# POWER_REG.net
KiCad netlist of a schematic drawn in Altium Designer
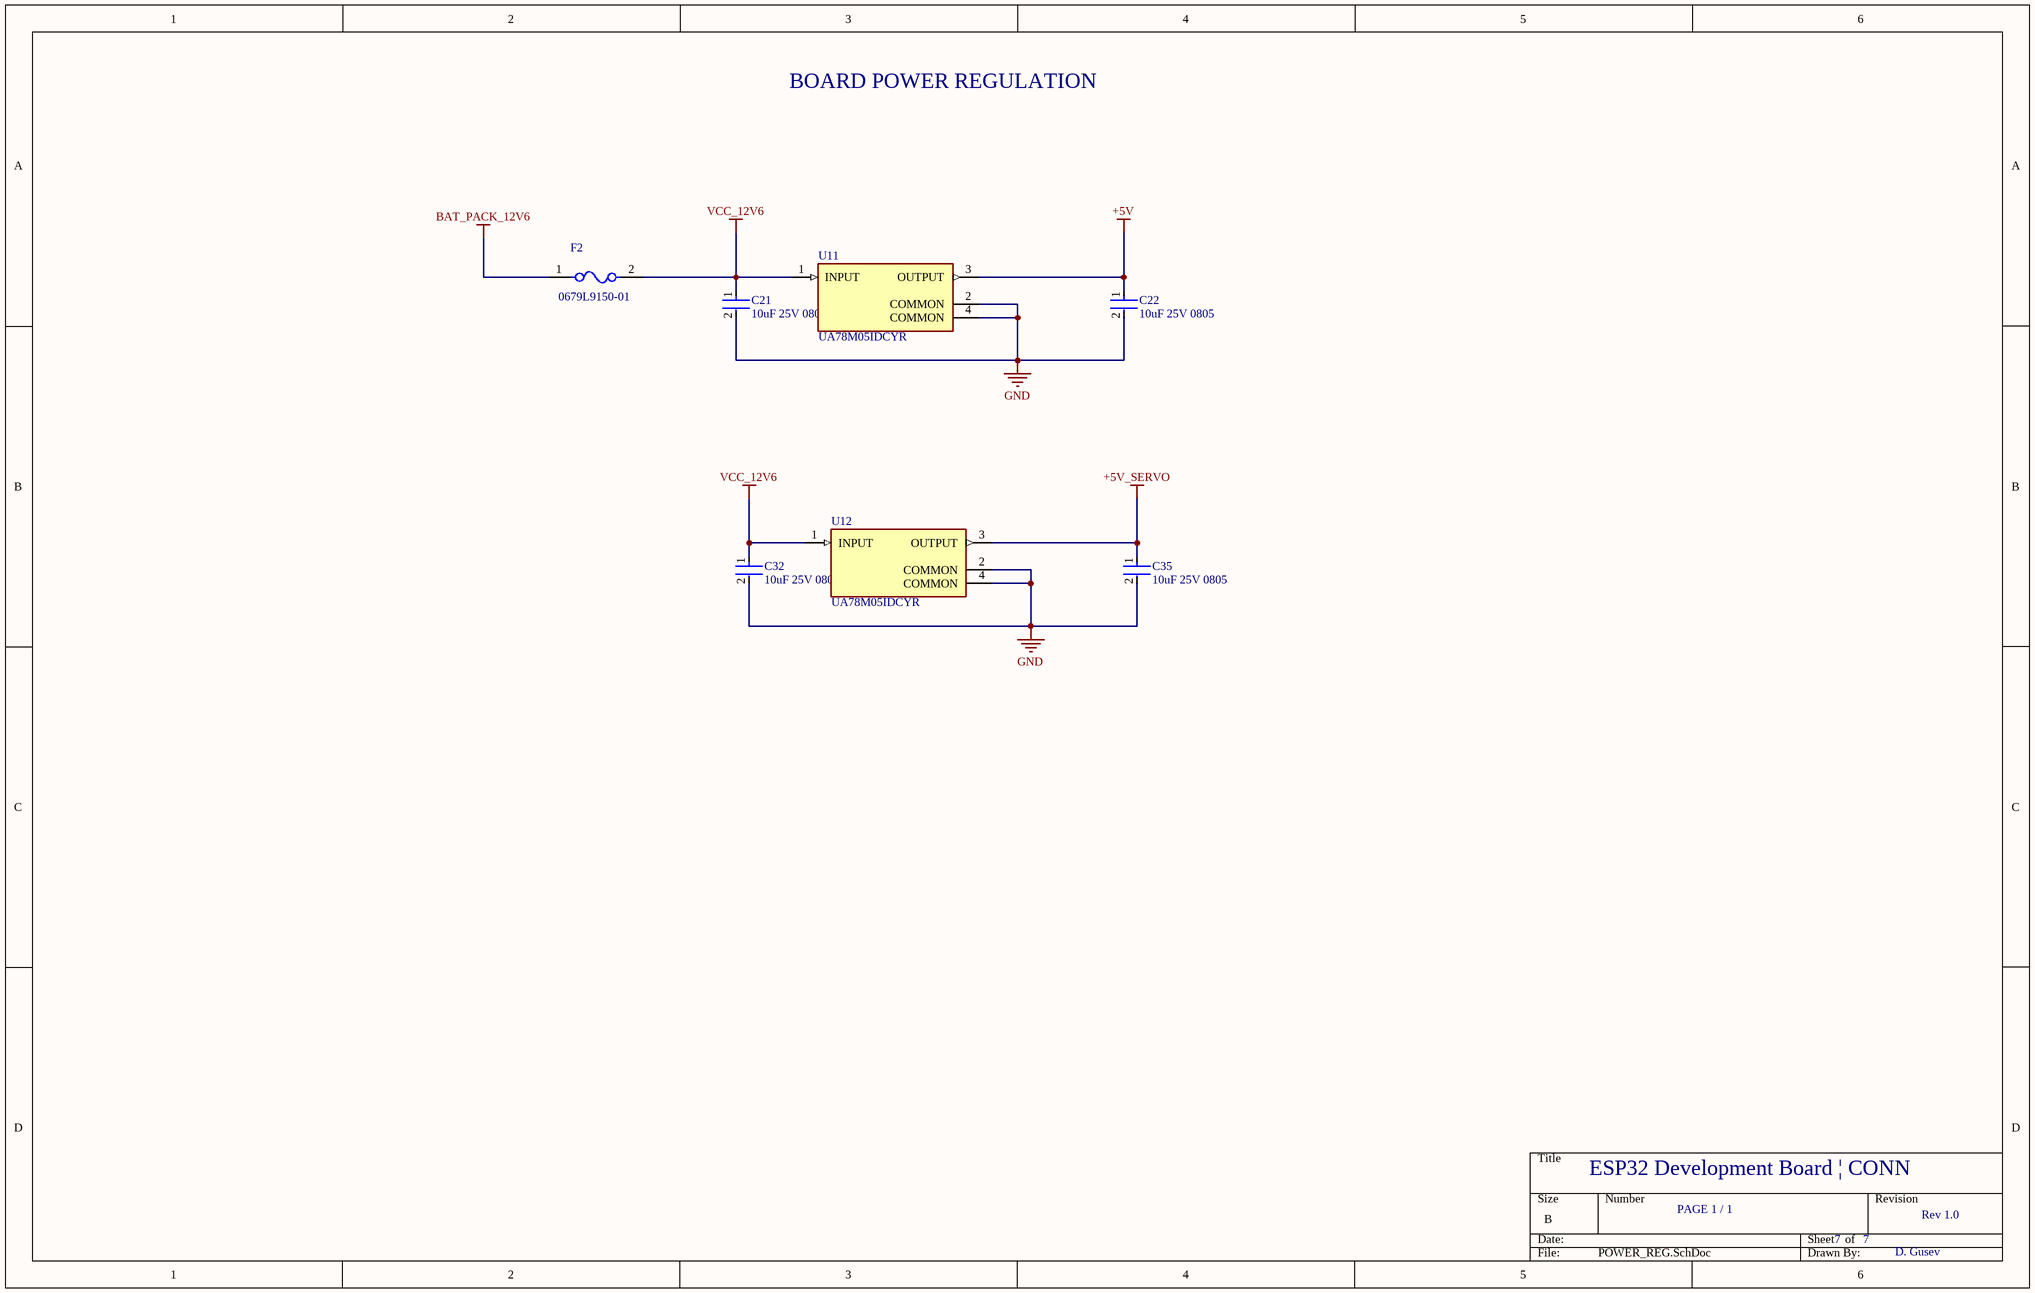
[diagram p0: POWER_REG.SchDoc]

(export (version "E")
  (design (tool "Eeschema 10.0.6"))
  (components
    (comp (ref "C21")
      (value "10uF 25V 0805")
      (footprint "FP-GRM21B-0_15-IPC_C")
      (description "Chip Multilayer Ceramic Capacitors for General Purpose, 0805, 10uF, X5R, 15%, 10%, 25V")
      (fields (field (name "VOLTAGE") "25V") (field (name "TOLERANCE") "10%"))
      (libsource (lib "Altium Content Vault") (part "b4654b650e69147ec39a6b967a45e02"))
    )
    (comp (ref "C22")
      (value "10uF 25V 0805")
      (footprint "FP-GRM21B-0_15-IPC_C")
      (description "Chip Multilayer Ceramic Capacitors for General Purpose, 0805, 10uF, X5R, 15%, 10%, 25V")
      (fields (field (name "VOLTAGE") "25V") (field (name "TOLERANCE") "10%"))
      (libsource (lib "Altium Content Vault") (part "b4654b650e69147ec39a6b967a45e02"))
    )
    (comp (ref "C32")
      (value "10uF 25V 0805")
      (footprint "FP-GRM21B-0_15-IPC_C")
      (description "Chip Multilayer Ceramic Capacitors for General Purpose, 0805, 10uF, X5R, 15%, 10%, 25V")
      (fields (field (name "VOLTAGE") "25V") (field (name "TOLERANCE") "10%"))
      (libsource (lib "Altium Content Vault") (part "b4654b650e69147ec39a6b967a45e02"))
    )
    (comp (ref "C35")
      (value "10uF 25V 0805")
      (footprint "FP-GRM21B-0_15-IPC_C")
      (description "Chip Multilayer Ceramic Capacitors for General Purpose, 0805, 10uF, X5R, 15%, 10%, 25V")
      (fields (field (name "VOLTAGE") "25V") (field (name "TOLERANCE") "10%"))
      (libsource (lib "Altium Content Vault") (part "b4654b650e69147ec39a6b967a45e02"))
    )
    (comp (ref "F2")
      (value "0679L9150-01")
      (footprint "FP-0679L-MFG")
      (description "FUSE BRD MNT 15A 125VAC/VDC")
      (fields
        (field (name "OCTOPART") "https://octopart.com/0679l9150-01-bel+fuse-70850665")
        (field (name "MANUFACTURER") "Bel Fuse")
      )
      (libsource (lib "Altium Content Vault") (part "5bcf9b9f640e542cf0359d10258e979"))
    )
    (comp (ref "U11")
      (value "UA78M05IDCYR")
      (footprint "FP-DCY0004A-MFG")
      (description "IC REG LINEAR 5V 500MA SOT223-4")
      (fields
        (field (name "OCTOPART") "https://octopart.com/ua78m05idcyr-texas+instruments-525575")
        (field (name "MANUFACTURER") "Texas Instruments")
      )
      (libsource (lib "Altium Content Vault") (part "8ae96a6a62262bf838d5da5965c01e6"))
    )
    (comp (ref "U12")
      (value "UA78M05IDCYR")
      (footprint "FP-DCY0004A-MFG")
      (description "IC REG LINEAR 5V 500MA SOT223-4")
      (fields
        (field (name "OCTOPART") "https://octopart.com/ua78m05idcyr-texas+instruments-525575")
        (field (name "MANUFACTURER") "Texas Instruments")
      )
      (libsource (lib "Altium Content Vault") (part "8ae96a6a62262bf838d5da5965c01e6"))
    )
  )
  (nets
    (net (code "1") (name "+5V") (class "Default")
      (node (ref "C22") (pin "1") (pinfunction "1_1") (pintype "passive"))
      (node (ref "U11") (pin "3") (pinfunction "OUTPUT_3") (pintype "output"))
    )
    (net (code "2") (name "+5V_SERVO") (class "Default")
      (node (ref "C35") (pin "1") (pinfunction "1_1") (pintype "passive"))
      (node (ref "U12") (pin "3") (pinfunction "OUTPUT_3") (pintype "output"))
    )
    (net (code "3") (name "BAT_PACK_12V6") (class "Default")
      (node (ref "F2") (pin "1") (pinfunction "1_1") (pintype "passive"))
    )
    (net (code "4") (name "GND") (class "Default")
      (node (ref "C21") (pin "2") (pinfunction "2_2") (pintype "passive"))
      (node (ref "C22") (pin "2") (pinfunction "2_2") (pintype "passive"))
      (node (ref "C32") (pin "2") (pinfunction "2_2") (pintype "passive"))
      (node (ref "C35") (pin "2") (pinfunction "2_2") (pintype "passive"))
      (node (ref "U11") (pin "2") (pinfunction "COMMON_2") (pintype "passive"))
      (node (ref "U11") (pin "4") (pinfunction "COMMON_4") (pintype "passive"))
      (node (ref "U12") (pin "2") (pinfunction "COMMON_2") (pintype "passive"))
      (node (ref "U12") (pin "4") (pinfunction "COMMON_4") (pintype "passive"))
    )
    (net (code "5") (name "VCC_12V6") (class "Default")
      (node (ref "C21") (pin "1") (pinfunction "1_1") (pintype "passive"))
      (node (ref "C32") (pin "1") (pinfunction "1_1") (pintype "passive"))
      (node (ref "F2") (pin "2") (pinfunction "2_2") (pintype "passive"))
      (node (ref "U11") (pin "1") (pinfunction "INPUT_1") (pintype "input"))
      (node (ref "U12") (pin "1") (pinfunction "INPUT_1") (pintype "input"))
    )
  )
)
